# tuch-tablotara.net
KiCad netlist of a schematic drawn in Altium Designer
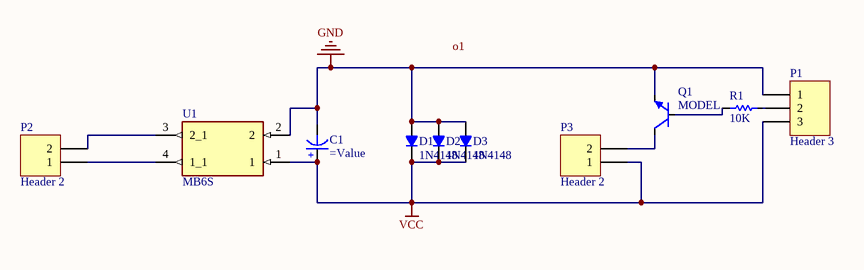
[diagram p0: tuch-tablotara.SchDoc]

(export (version "E")
  (design (tool "Eeschema 10.0.6"))
  (components
    (comp (ref "C1")
      (value "~")
      (footprint "ELEC-CAP-RAD10-20")
      (description "Electrolytic Capacitor")
      (libsource (lib "AltiumLib1") (part "Capacitor Electrolytic"))
    )
    (comp (ref "D1")
      (value "MODEL")
      (footprint "DO-41")
      (description "Diode")
      (fields (field (name "MODEL") "1N4148"))
      (libsource (lib "AltiumLib1") (part "Diode"))
    )
    (comp (ref "D2")
      (value "MODEL")
      (footprint "DO-41")
      (description "Diode")
      (fields (field (name "MODEL") "1N4148"))
      (libsource (lib "AltiumLib1") (part "Diode"))
    )
    (comp (ref "D3")
      (value "MODEL")
      (footprint "DO-41")
      (description "Diode")
      (fields (field (name "MODEL") "1N4148"))
      (libsource (lib "AltiumLib1") (part "Diode"))
    )
    (comp (ref "P1")
      (value "Header 3")
      (footprint "HDR1X3")
      (description "Header, 3-Pin")
      (fields (field (name "PUBLISHER") "Altium Limited"))
      (libsource (lib "Miscellaneous Connectors") (part "Header 3"))
    )
    (comp (ref "P2")
      (value "Header 2")
      (footprint "HDR1X2")
      (description "Header, 2-Pin")
      (fields (field (name "PUBLISHER") "Altium Limited"))
      (libsource (lib "Miscellaneous Connectors") (part "Header 2"))
    )
    (comp (ref "P3")
      (value "Header 2")
      (footprint "HDR1X2")
      (description "Header, 2-Pin")
      (fields (field (name "PUBLISHER") "Altium Limited"))
      (libsource (lib "Miscellaneous Connectors") (part "Header 2"))
    )
    (comp (ref "Q1")
      (value "MODEL")
      (footprint "SOT32")
      (description "NPN Bipolar Transistor")
      (libsource (lib "AltiumLib1") (part "BD139"))
    )
    (comp (ref "R1")
      (value "10K")
      (footprint "RES 1206 (3216X08L)")
      (description "Resistor")
      (fields (field (name "TOLERANCE") "5%") (field (name "POWER") "1/4 W"))
      (libsource (lib "AltiumLib1") (part "Resistor"))
    )
    (comp (ref "U1")
      (value "MB6S")
      (footprint "SOIC245P670X270-4N")
      (description "Bridge Rectifier Single Phase Standard 600V Surface Mount 4-SOIC")
      (fields (field (name "MF") "ON Semiconductor") (field (name "DIGI-KEY_PART_NUMBER") "MB6SCT-ND"))
      (libsource (lib "MB6S") (part "MB6S"))
    )
  )
  (nets
    (net (code "2") (name "GND") (class "Default")
      (node (ref "C1") (pin "1") (pinfunction "-_1") (pintype "passive"))
      (node (ref "D1") (pin "1") (pinfunction "A_1") (pintype "passive"))
      (node (ref "D2") (pin "1") (pinfunction "A_1") (pintype "passive"))
      (node (ref "D3") (pin "1") (pinfunction "A_1") (pintype "passive"))
      (node (ref "P1") (pin "1") (pinfunction "1_1") (pintype "passive"))
      (node (ref "Q1") (pin "1") (pinfunction "E_1") (pintype "passive"))
      (node (ref "U1") (pin "2") (pinfunction "2_2") (pintype "input"))
    )
    (net (code "3") (name "Net-(P1-Pad2)") (class "Default")
      (node (ref "P1") (pin "2") (pinfunction "2_2") (pintype "passive"))
      (node (ref "R1") (pin "1") (pinfunction "1_1") (pintype "passive"))
    )
    (net (code "4") (name "Net-(Q1-B)") (class "Default")
      (node (ref "Q1") (pin "3") (pinfunction "B_3") (pintype "passive"))
      (node (ref "R1") (pin "2") (pinfunction "2_2") (pintype "passive"))
    )
    (net (code "5") (name "Net-(Q1-C)") (class "Default")
      (node (ref "P3") (pin "2") (pinfunction "2_2") (pintype "passive"))
      (node (ref "Q1") (pin "2") (pinfunction "C_2") (pintype "passive"))
    )
    (net (code "6") (name "Net-(U1-1_1)") (class "Default")
      (node (ref "P2") (pin "1") (pinfunction "1_1") (pintype "passive"))
      (node (ref "U1") (pin "4") (pinfunction "1_1_4") (pintype "output"))
    )
    (net (code "7") (name "Net-(U1-2_1)") (class "Default")
      (node (ref "P2") (pin "2") (pinfunction "2_2") (pintype "passive"))
      (node (ref "U1") (pin "3") (pinfunction "2_1_3") (pintype "output"))
    )
    (net (code "8") (name "VCC") (class "Default")
      (node (ref "C1") (pin "2") (pinfunction "+_2") (pintype "passive"))
      (node (ref "D1") (pin "2") (pinfunction "K_2") (pintype "passive"))
      (node (ref "D2") (pin "2") (pinfunction "K_2") (pintype "passive"))
      (node (ref "D3") (pin "2") (pinfunction "K_2") (pintype "passive"))
      (node (ref "P1") (pin "3") (pinfunction "3_3") (pintype "passive"))
      (node (ref "P3") (pin "1") (pinfunction "1_1") (pintype "passive"))
      (node (ref "U1") (pin "1") (pinfunction "1_1") (pintype "input"))
    )
  )
)
